# pita.net
KiCad netlist of a schematic drawn in EAGLE
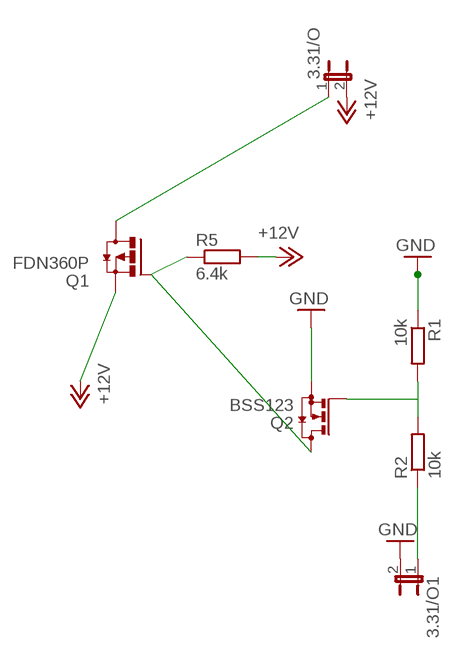
[diagram p0: schematic, sheet 1]

(export (version "E")
  (design (tool "Eeschema 10.0.6"))
  (components
    (comp (ref "3.31/O")
      (value "JP1E")
      (footprint "eagle-import:JP1")
      (libsource (lib "eagle-import") (part "JP1E"))
    )
    (comp (ref "3.31/O1")
      (value "JP1E")
      (footprint "eagle-import:JP1")
      (libsource (lib "eagle-import") (part "JP1E"))
    )
    (comp (ref "Q1")
      (value "FDN360P")
      (footprint "eagle-import:SUPER-SOT3")
      (libsource (lib "eagle-import") (part "FDN360P"))
    )
    (comp (ref "Q2")
      (value "BSS123")
      (footprint "eagle-import:SOT23")
      (libsource (lib "eagle-import") (part "BSS123"))
    )
    (comp (ref "R1")
      (value "10k")
      (footprint "eagle-import:0204_5")
      (libsource (lib "eagle-import") (part "R-EU_0204/5"))
    )
    (comp (ref "R2")
      (value "10k")
      (footprint "eagle-import:0204_5")
      (libsource (lib "eagle-import") (part "R-EU_0204/5"))
    )
    (comp (ref "R5")
      (value "6.4k")
      (footprint "eagle-import:0204_7")
      (libsource (lib "eagle-import") (part "R-EU_0204/7"))
    )
  )
  (nets
    (net (code "1") (name "+12V") (class "Default")
      (node (ref "3.31/O") (pin "2") (pinfunction "2_2") (pintype "passive"))
      (node (ref "Q1") (pin "2") (pinfunction "S_2") (pintype "passive"))
      (node (ref "R5") (pin "2") (pinfunction "2_2") (pintype "passive"))
    )
    (net (code "2") (name "GND") (class "Default")
      (node (ref "3.31/O1") (pin "2") (pinfunction "2_2") (pintype "passive"))
      (node (ref "Q2") (pin "2") (pinfunction "S_2") (pintype "passive"))
      (node (ref "R1") (pin "1") (pinfunction "1_1") (pintype "passive"))
    )
    (net (code "3") (name "Net-(3.31/O1-Pad1)") (class "Default")
      (node (ref "3.31/O1") (pin "1") (pinfunction "1_1") (pintype "passive"))
      (node (ref "R2") (pin "1") (pinfunction "1_1") (pintype "passive"))
    )
    (net (code "4") (name "Net-(Q1-D)") (class "Default")
      (node (ref "3.31/O") (pin "1") (pinfunction "1_1") (pintype "passive"))
      (node (ref "Q1") (pin "3") (pinfunction "D_3") (pintype "passive"))
    )
    (net (code "5") (name "Net-(Q1-G)") (class "Default")
      (node (ref "Q1") (pin "1") (pinfunction "G_1") (pintype "passive"))
      (node (ref "Q2") (pin "3") (pinfunction "D_3") (pintype "passive"))
      (node (ref "R5") (pin "1") (pinfunction "1_1") (pintype "passive"))
    )
    (net (code "6") (name "Net-(Q2-G)") (class "Default")
      (node (ref "Q2") (pin "1") (pinfunction "G_1") (pintype "passive"))
      (node (ref "R1") (pin "2") (pinfunction "2_2") (pintype "passive"))
      (node (ref "R2") (pin "2") (pinfunction "2_2") (pintype "passive"))
    )
  )
)
